# 1-Schematic_Universal_3D_Printer_PDB.net
KiCad netlist of a schematic drawn in EasyEDA
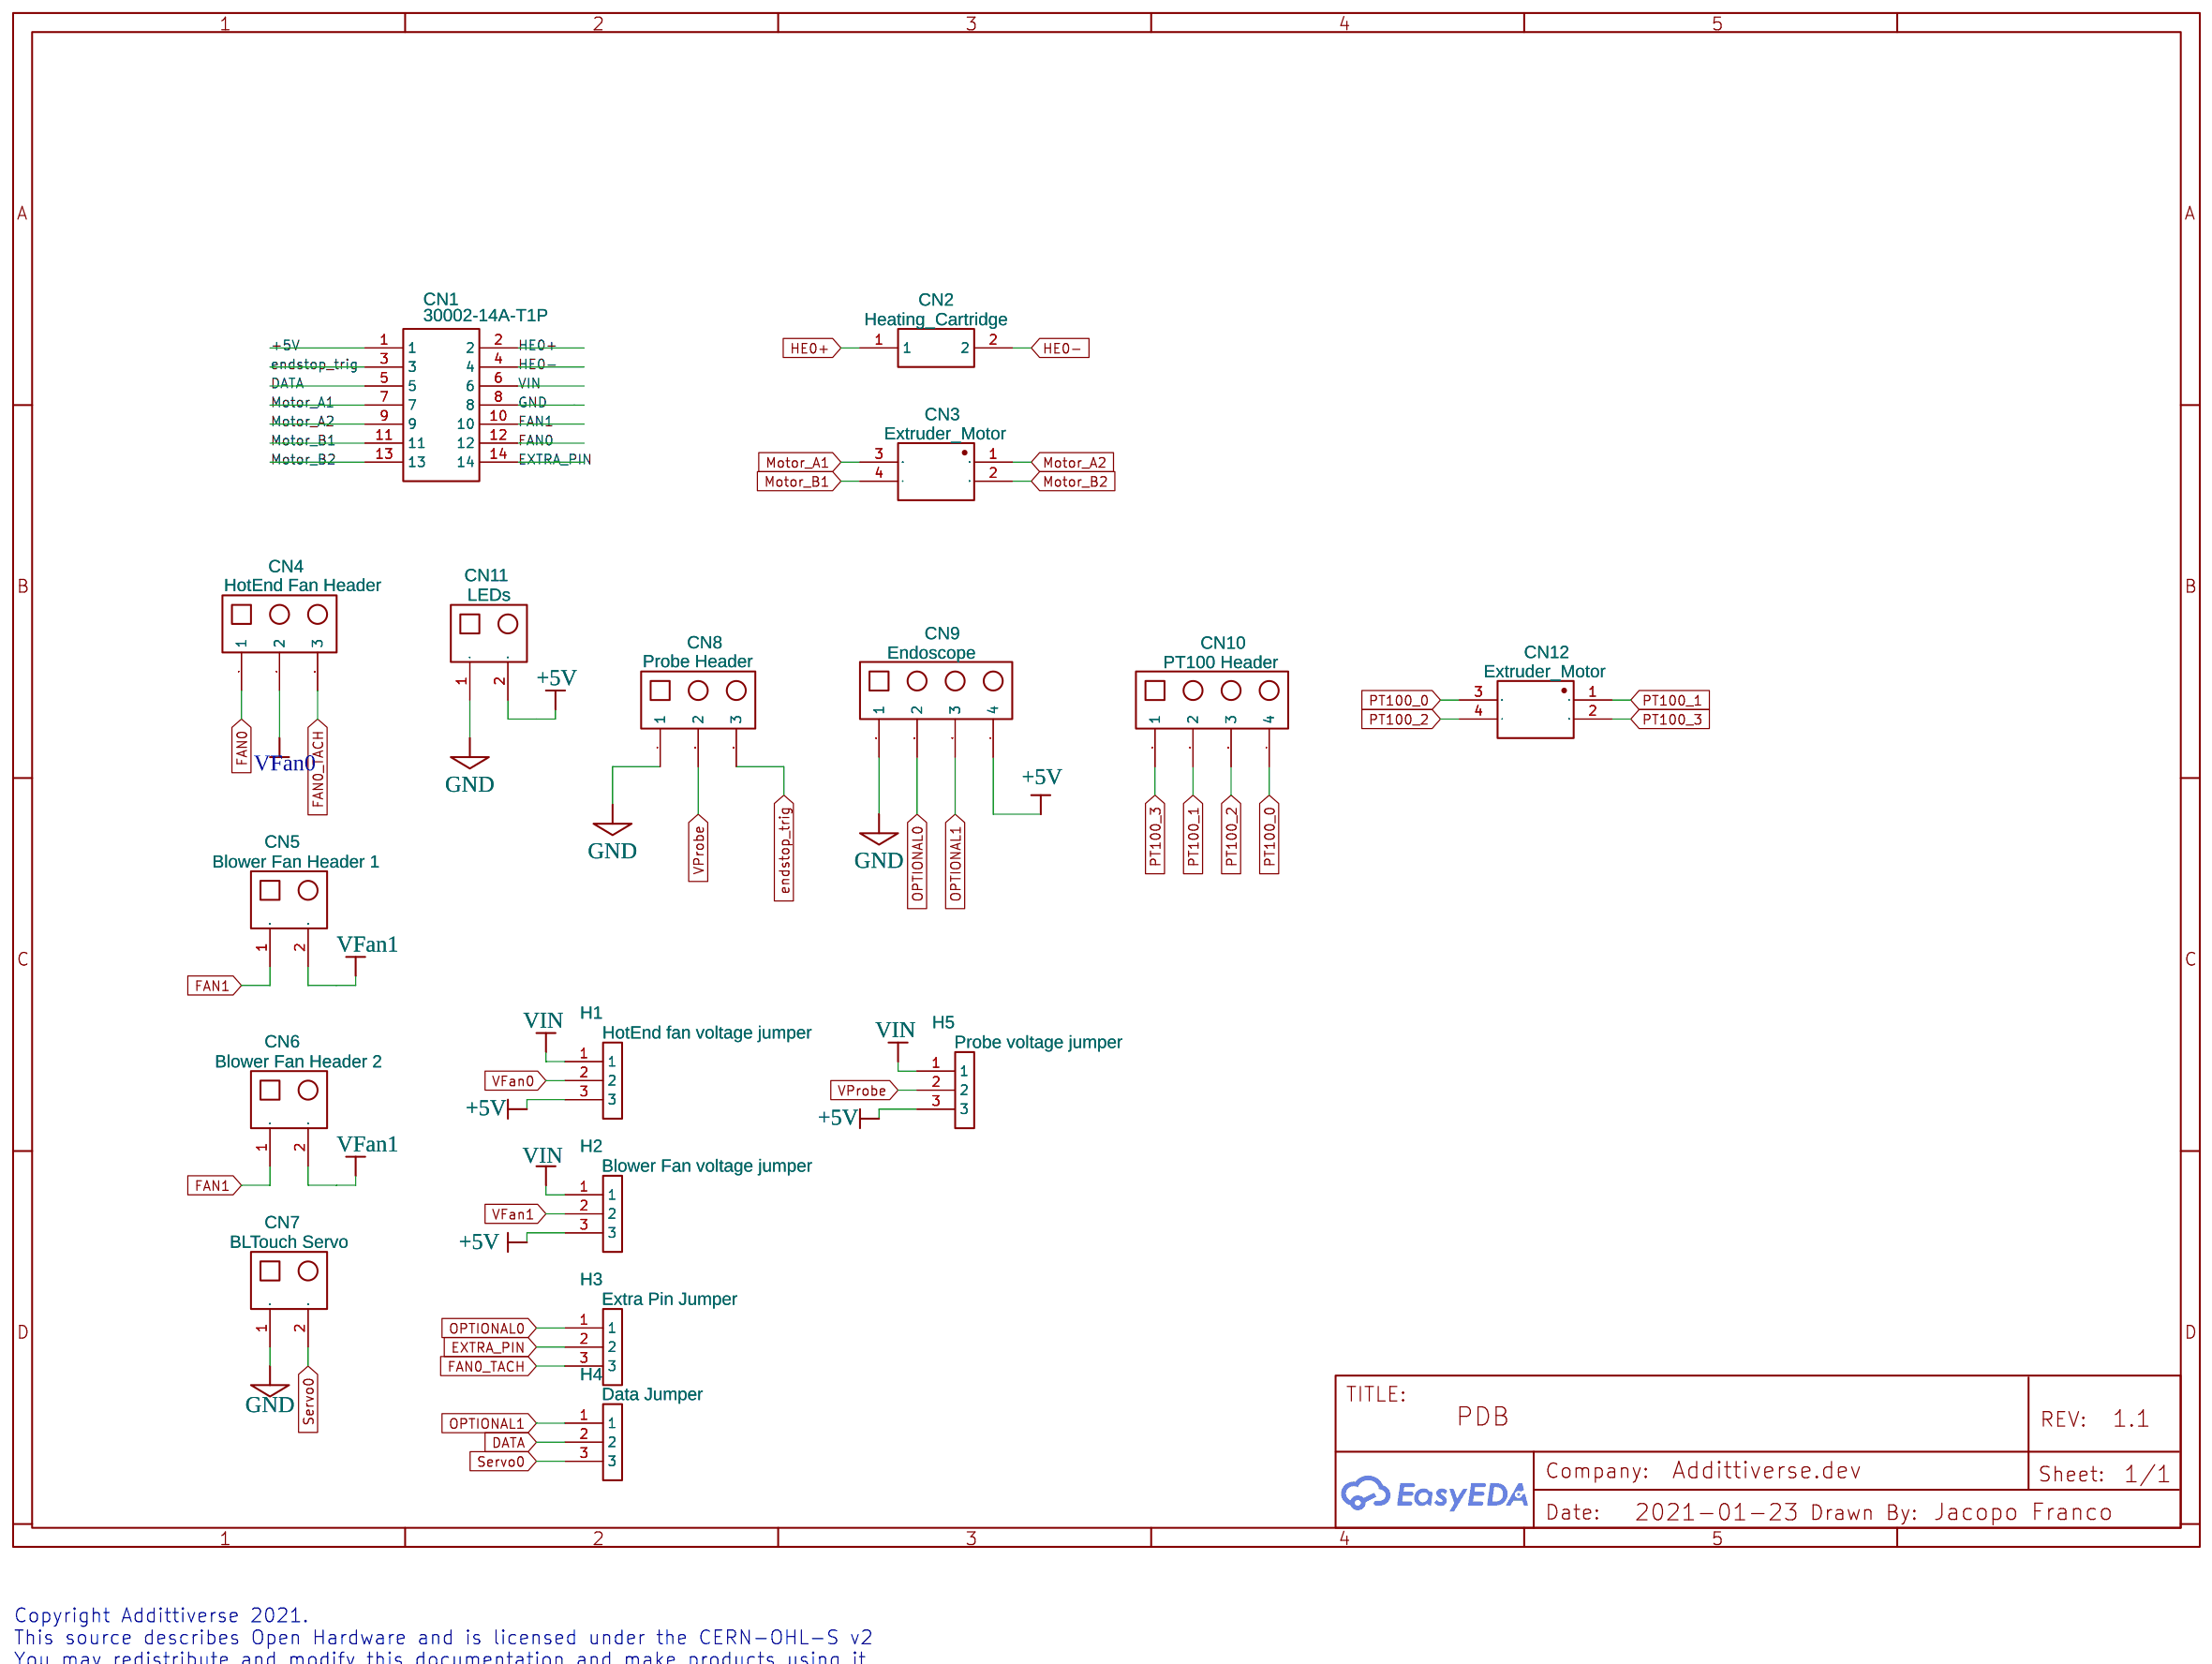
[diagram p0: schematic sheet]

(export (version "E")
  (design (tool "Eeschema 10.0.6"))
  (components
    (comp (ref "CN1")
      (value "30002-14A-T1P")
      (fields (field (name "BOM_Supplier Part") "C185094"))
      (libsource (lib "") (part "30002-14A-T1P"))
    )
    (comp (ref "CN2")
      (value "Heating_Cartridge")
      (fields
        (field (name "BOM_Manufacturer Part") "0430450200")
        (field (name "BOM_Supplier Part") "C122431")
      )
      (libsource (lib "") (part "0430450200"))
    )
    (comp (ref "CN3")
      (value "Extruder_Motor")
      (fields (field (name "BOM_Manufacturer Part") "430450427") (field (name "BOM_Supplier Part") "C293536"))
      (libsource (lib "") (part "430450427"))
    )
    (comp (ref "CN4")
      (value "HotEnd Fan Header")
      (fields (field (name "BOM_Manufacturer Part") "JST_XH CONNECTOR"))
      (libsource (lib "") (part "JST_XH CONNECTOR 3"))
    )
    (comp (ref "CN5")
      (value "Blower Fan Header 1")
      (fields (field (name "BOM_Manufacturer Part") "XH_2P_CONNECTOR"))
      (libsource (lib "") (part "JST XH 2PIN"))
    )
    (comp (ref "CN6")
      (value "Blower Fan Header 2")
      (fields (field (name "BOM_Manufacturer Part") "XH_2P_CONNECTOR"))
      (libsource (lib "") (part "JST XH 2PIN"))
    )
    (comp (ref "CN7")
      (value "BLTouch Servo")
      (fields (field (name "BOM_Manufacturer Part") "XH_2P_CONNECTOR"))
      (libsource (lib "") (part "JST XH 2PIN"))
    )
    (comp (ref "CN8")
      (value "Probe Header")
      (fields (field (name "BOM_Manufacturer Part") "JST_XH CONNECTOR"))
      (libsource (lib "") (part "JST_XH CONNECTOR 3"))
    )
    (comp (ref "CN9")
      (value "Endoscope")
      (fields (field (name "BOM_Manufacturer Part") "JST_XH CONNECTOR"))
      (libsource (lib "") (part "JST XH-04"))
    )
    (comp (ref "CN10")
      (value "PT100 Header")
      (fields (field (name "BOM_Manufacturer Part") "JST_XH CONNECTOR"))
      (libsource (lib "") (part "JST XH-04"))
    )
    (comp (ref "CN11")
      (value "LEDs")
      (fields (field (name "BOM_Manufacturer Part") "XH_2P_CONNECTOR"))
      (libsource (lib "") (part "JST XH 2PIN"))
    )
    (comp (ref "CN12")
      (value "Extruder_Motor")
      (fields (field (name "BOM_Manufacturer Part") "430450427") (field (name "BOM_Supplier Part") "C293536"))
      (libsource (lib "") (part "430450427"))
    )
    (comp (ref "H1")
      (value "HotEnd fan voltage jumper")
      (fields (field (name "BOM_Manufacturer Part") "Header 3P 2.54mm"))
      (libsource (lib "") (part "Header 3P 2.54mm"))
    )
    (comp (ref "H2")
      (value "Blower Fan voltage jumper")
      (fields (field (name "BOM_Manufacturer Part") "Header 3P 2.54mm"))
      (libsource (lib "") (part "Header 3P 2.54mm"))
    )
    (comp (ref "H3")
      (value "Extra Pin Jumper")
      (fields (field (name "BOM_Manufacturer Part") "Header 3P 2.54mm"))
      (libsource (lib "") (part "Header 3P 2.54mm"))
    )
    (comp (ref "H4")
      (value "Data Jumper")
      (fields (field (name "BOM_Manufacturer Part") "Header 3P 2.54mm"))
      (libsource (lib "") (part "Header 3P 2.54mm"))
    )
    (comp (ref "H5")
      (value "Probe voltage jumper")
      (fields (field (name "BOM_Manufacturer Part") "Header 3P 2.54mm"))
      (libsource (lib "") (part "Header 3P 2.54mm"))
    )
  )
  (nets
    (net (code "1") (name "+5V") (class "Default")
      (node (ref "CN1") (pin "1") (pinfunction "1_1") (pintype "unspecified"))
      (node (ref "CN11") (pin "2") (pinfunction "2_2") (pintype "unspecified"))
      (node (ref "CN9") (pin "4") (pinfunction "4_4") (pintype "unspecified"))
      (node (ref "H1") (pin "3") (pinfunction "3_3") (pintype "unspecified"))
      (node (ref "H2") (pin "3") (pinfunction "3_3") (pintype "unspecified"))
      (node (ref "H5") (pin "3") (pinfunction "3_3") (pintype "unspecified"))
    )
    (net (code "2") (name "DATA") (class "Default")
      (node (ref "CN1") (pin "5") (pinfunction "5_5") (pintype "unspecified"))
      (node (ref "H4") (pin "2") (pinfunction "2_2") (pintype "unspecified"))
    )
    (net (code "3") (name "EXTRA_PIN") (class "Default")
      (node (ref "CN1") (pin "14") (pinfunction "14_14") (pintype "unspecified"))
      (node (ref "H3") (pin "2") (pinfunction "2_2") (pintype "unspecified"))
    )
    (net (code "4") (name "FAN0") (class "Default")
      (node (ref "CN1") (pin "12") (pinfunction "12_12") (pintype "unspecified"))
      (node (ref "CN4") (pin "1") (pinfunction "1_1") (pintype "unspecified"))
    )
    (net (code "5") (name "FAN0_TACH") (class "Default")
      (node (ref "CN4") (pin "3") (pinfunction "3_3") (pintype "unspecified"))
      (node (ref "H3") (pin "3") (pinfunction "3_3") (pintype "unspecified"))
    )
    (net (code "6") (name "FAN1") (class "Default")
      (node (ref "CN1") (pin "10") (pinfunction "10_10") (pintype "unspecified"))
      (node (ref "CN5") (pin "1") (pinfunction "1_1") (pintype "unspecified"))
      (node (ref "CN6") (pin "1") (pinfunction "1_1") (pintype "unspecified"))
    )
    (net (code "7") (name "GND") (class "Default")
      (node (ref "CN1") (pin "8") (pinfunction "8_8") (pintype "unspecified"))
      (node (ref "CN11") (pin "1") (pinfunction "1_1") (pintype "unspecified"))
      (node (ref "CN7") (pin "1") (pinfunction "1_1") (pintype "unspecified"))
      (node (ref "CN8") (pin "1") (pinfunction "1_1") (pintype "unspecified"))
      (node (ref "CN9") (pin "1") (pinfunction "1_1") (pintype "unspecified"))
    )
    (net (code "8") (name "HE0+") (class "Default")
      (node (ref "CN1") (pin "2") (pinfunction "2_2") (pintype "unspecified"))
      (node (ref "CN2") (pin "1") (pinfunction "1_1") (pintype "unspecified"))
    )
    (net (code "9") (name "HE0-") (class "Default")
      (node (ref "CN1") (pin "4") (pinfunction "4_4") (pintype "unspecified"))
      (node (ref "CN2") (pin "2") (pinfunction "2_2") (pintype "unspecified"))
    )
    (net (code "10") (name "Motor_A1") (class "Default")
      (node (ref "CN1") (pin "7") (pinfunction "7_7") (pintype "unspecified"))
      (node (ref "CN3") (pin "3") (pinfunction "3_3") (pintype "unspecified"))
    )
    (net (code "11") (name "Motor_A2") (class "Default")
      (node (ref "CN1") (pin "9") (pinfunction "9_9") (pintype "unspecified"))
      (node (ref "CN3") (pin "1") (pinfunction "1_1") (pintype "unspecified"))
    )
    (net (code "12") (name "Motor_B1") (class "Default")
      (node (ref "CN1") (pin "11") (pinfunction "11_11") (pintype "unspecified"))
      (node (ref "CN3") (pin "4") (pinfunction "4_4") (pintype "unspecified"))
    )
    (net (code "13") (name "Motor_B2") (class "Default")
      (node (ref "CN1") (pin "13") (pinfunction "13_13") (pintype "unspecified"))
      (node (ref "CN3") (pin "2") (pinfunction "2_2") (pintype "unspecified"))
    )
    (net (code "14") (name "OPTIONAL0") (class "Default")
      (node (ref "CN9") (pin "2") (pinfunction "2_2") (pintype "unspecified"))
      (node (ref "H3") (pin "1") (pinfunction "1_1") (pintype "unspecified"))
    )
    (net (code "15") (name "OPTIONAL1") (class "Default")
      (node (ref "CN9") (pin "3") (pinfunction "3_3") (pintype "unspecified"))
      (node (ref "H4") (pin "1") (pinfunction "1_1") (pintype "unspecified"))
    )
    (net (code "16") (name "PT100_0") (class "Default")
      (node (ref "CN10") (pin "4") (pinfunction "4_4") (pintype "unspecified"))
      (node (ref "CN12") (pin "3") (pinfunction "3_3") (pintype "unspecified"))
    )
    (net (code "17") (name "PT100_1") (class "Default")
      (node (ref "CN10") (pin "2") (pinfunction "2_2") (pintype "unspecified"))
      (node (ref "CN12") (pin "1") (pinfunction "1_1") (pintype "unspecified"))
    )
    (net (code "18") (name "PT100_2") (class "Default")
      (node (ref "CN10") (pin "3") (pinfunction "3_3") (pintype "unspecified"))
      (node (ref "CN12") (pin "4") (pinfunction "4_4") (pintype "unspecified"))
    )
    (net (code "19") (name "PT100_3") (class "Default")
      (node (ref "CN10") (pin "1") (pinfunction "1_1") (pintype "unspecified"))
      (node (ref "CN12") (pin "2") (pinfunction "2_2") (pintype "unspecified"))
    )
    (net (code "20") (name "Servo0") (class "Default")
      (node (ref "CN7") (pin "2") (pinfunction "2_2") (pintype "unspecified"))
      (node (ref "H4") (pin "3") (pinfunction "3_3") (pintype "unspecified"))
    )
    (net (code "21") (name "VFan0") (class "Default")
      (node (ref "CN4") (pin "2") (pinfunction "2_2") (pintype "unspecified"))
      (node (ref "H1") (pin "2") (pinfunction "2_2") (pintype "unspecified"))
    )
    (net (code "22") (name "VFan1") (class "Default")
      (node (ref "CN5") (pin "2") (pinfunction "2_2") (pintype "unspecified"))
      (node (ref "CN6") (pin "2") (pinfunction "2_2") (pintype "unspecified"))
      (node (ref "H2") (pin "2") (pinfunction "2_2") (pintype "unspecified"))
    )
    (net (code "23") (name "VIN") (class "Default")
      (node (ref "CN1") (pin "6") (pinfunction "6_6") (pintype "unspecified"))
      (node (ref "H1") (pin "1") (pinfunction "1_1") (pintype "unspecified"))
      (node (ref "H2") (pin "1") (pinfunction "1_1") (pintype "unspecified"))
      (node (ref "H5") (pin "1") (pinfunction "1_1") (pintype "unspecified"))
    )
    (net (code "24") (name "VProbe") (class "Default")
      (node (ref "CN8") (pin "2") (pinfunction "2_2") (pintype "unspecified"))
      (node (ref "H5") (pin "2") (pinfunction "2_2") (pintype "unspecified"))
    )
    (net (code "25") (name "endstop_trig") (class "Default")
      (node (ref "CN1") (pin "3") (pinfunction "3_3") (pintype "unspecified"))
      (node (ref "CN8") (pin "3") (pinfunction "3_3") (pintype "unspecified"))
    )
  )
)
